# Control.net
KiCad netlist of a schematic drawn in EAGLE
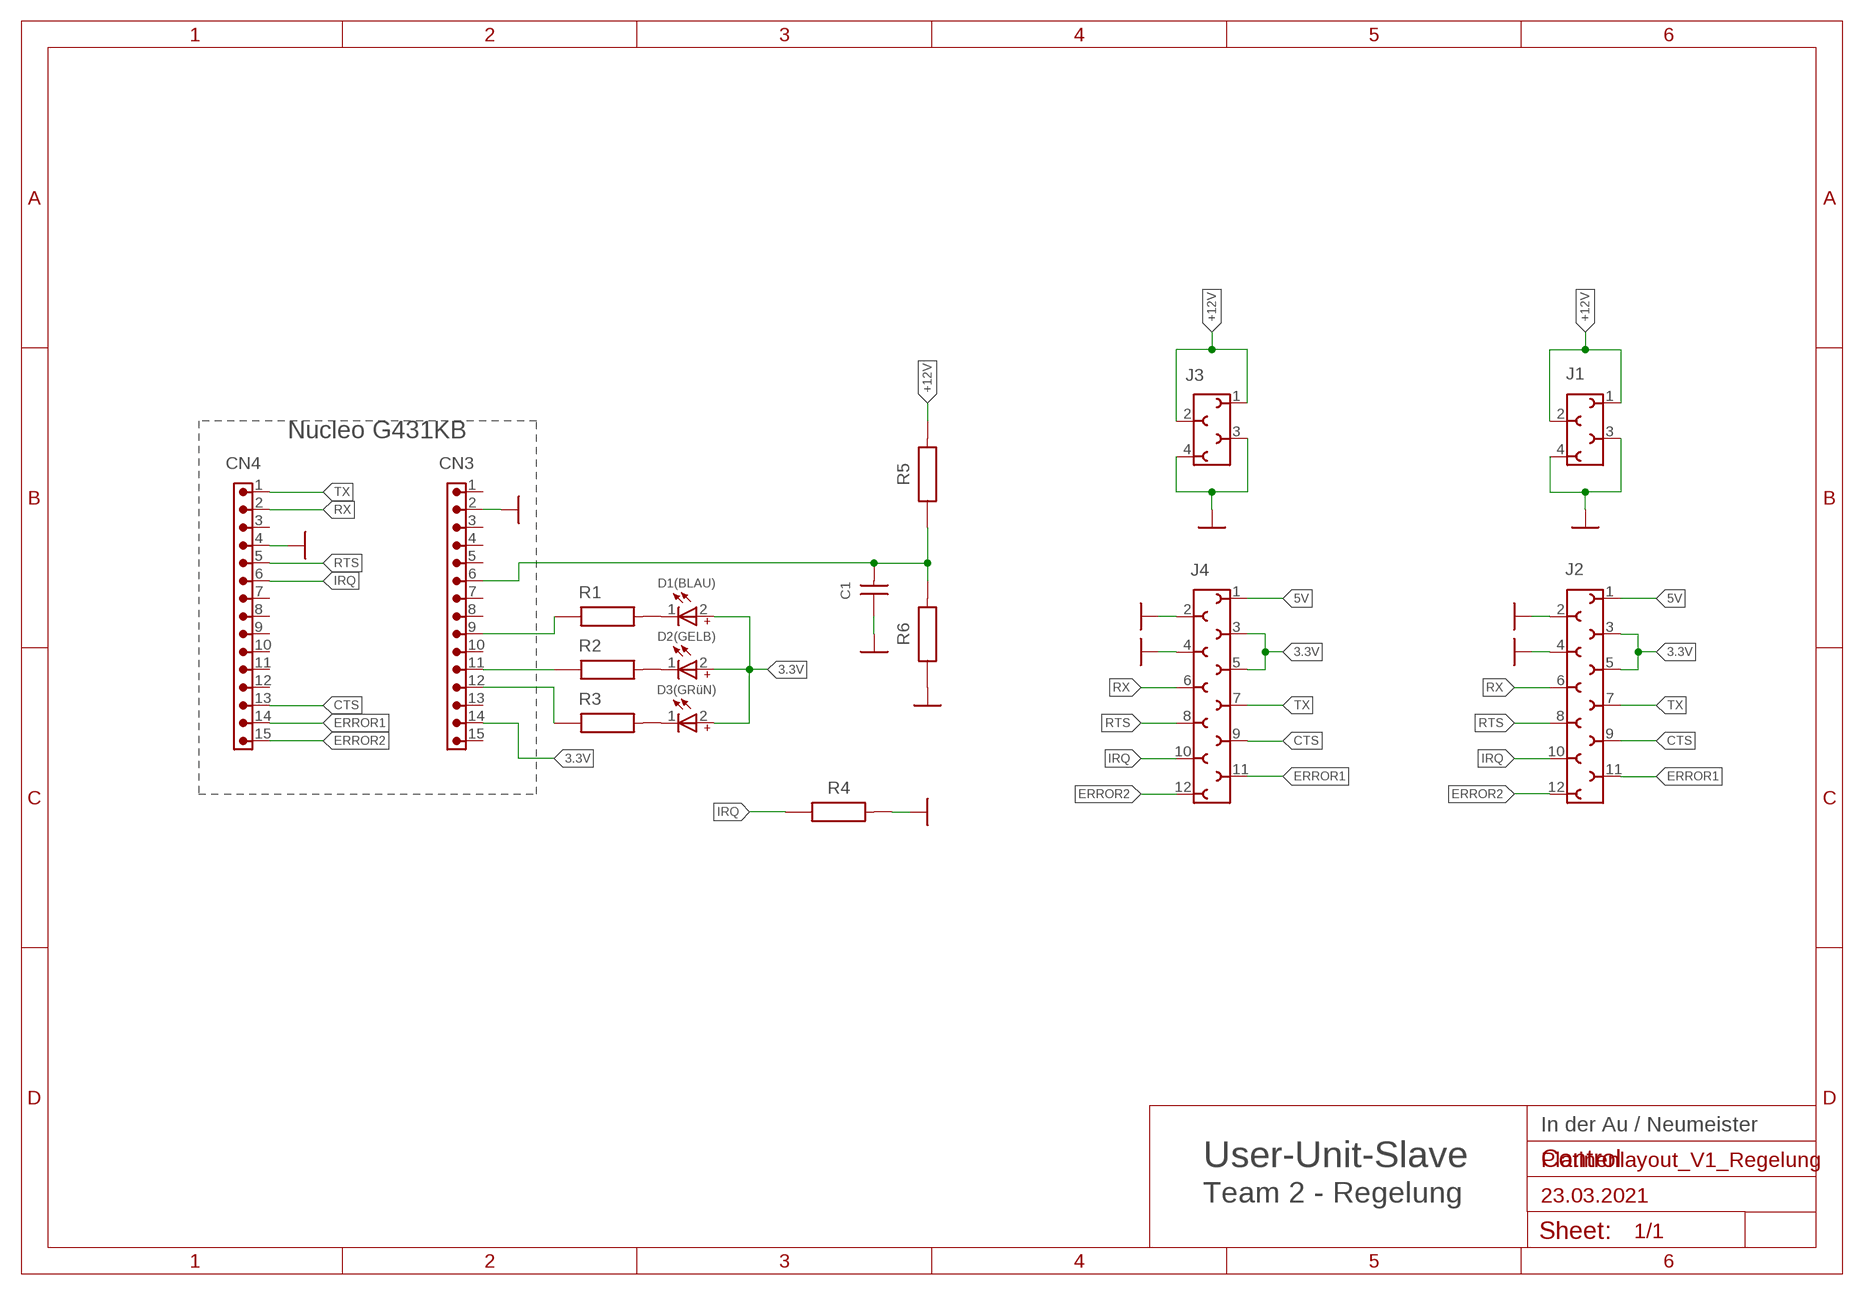
[diagram p0: schematic, sheet 1]

(export (version "E")
  (design (tool "Eeschema 10.0.6"))
  (components
    (comp (ref "C1")
      (value "10 nF")
      (footprint "eagle-import:WCAP-CSGP_1206_H1.25")
      (libsource (lib "eagle-import") (part "WCAP-CSGP_1206_H1.25_10V(DC)_885012008008"))
    )
    (comp (ref "CN3")
      (value "61301511121")
      (footprint "eagle-import:61301511121")
      (libsource (lib "eagle-import") (part "6130XX11121_61301511121"))
    )
    (comp (ref "CN4")
      (value "61301511121")
      (footprint "eagle-import:61301511121")
      (libsource (lib "eagle-import") (part "6130XX11121_61301511121"))
    )
    (comp (ref "D1(BLAU)")
      (value "WL-TMRC_3MM_151031SS06000_WITHOUTSTOPPER")
      (footprint "eagle-import:WL-TMRC_3MM")
      (fields (field (name "SPICEPREFIX") "D"))
      (libsource (lib "eagle-import") (part "WL-TMRC_3MM_WITHOUTSTOPPER_151031SS06000"))
    )
    (comp (ref "D2(GELB)")
      (value "WL-TMRC_3MM_151031YS06000_WITHOUTSTOPPER")
      (footprint "eagle-import:WL-TMRC_3MM")
      (libsource (lib "eagle-import") (part "WL-TMRC_3MM_WITHOUTSTOPPER_151031YS06000"))
    )
    (comp (ref "D3(GRüN)")
      (value "WL-TMRC_3MM_151031VS06000_WITHOUTSTOPPER")
      (footprint "eagle-import:WL-TMRC_3MM")
      (libsource (lib "eagle-import") (part "WL-TMRC_3MM_WITHOUTSTOPPER_151031VS06000"))
    )
    (comp (ref "J1")
      (value "6100XX11921_61000411921")
      (footprint "eagle-import:61000411921")
      (libsource (lib "eagle-import") (part "6100XX11921_61000411921"))
    )
    (comp (ref "J2")
      (value "6100XX11921_61001211921")
      (footprint "eagle-import:61001211921")
      (libsource (lib "eagle-import") (part "6100XX11921_61001211921"))
    )
    (comp (ref "J3")
      (value "690367290476")
      (footprint "eagle-import:690367290476")
      (libsource (lib "eagle-import") (part "690367290476"))
    )
    (comp (ref "J4")
      (value "690367291276")
      (footprint "eagle-import:690367291276")
      (libsource (lib "eagle-import") (part "690367291276"))
    )
    (comp (ref "R1")
      (value "1Ohm")
      (footprint "eagle-import:WRIS-KSKE_0805_2.0X1.25X0.6(LXWXH)")
      (libsource (lib "eagle-import") (part "WRIS-KSKE_0805_2.0X1.25X0.6_560050320011"))
    )
    (comp (ref "R2")
      (value "1Ohm")
      (footprint "eagle-import:WRIS-KSKE_0805_2.0X1.25X0.6(LXWXH)")
      (libsource (lib "eagle-import") (part "WRIS-KSKE_0805_2.0X1.25X0.6_560050320011"))
    )
    (comp (ref "R3")
      (value "1Ohm")
      (footprint "eagle-import:WRIS-KSKE_0805_2.0X1.25X0.6(LXWXH)")
      (libsource (lib "eagle-import") (part "WRIS-KSKE_0805_2.0X1.25X0.6_560050320011"))
    )
    (comp (ref "R4")
      (value "0.1Ohm")
      (footprint "eagle-import:WRIS-KSKE_0805_2.0X1.25X0.6(LXWXH)")
      (libsource (lib "eagle-import") (part "WRIS-KSKE_0805_2.0X1.25X0.6_560050320001"))
    )
    (comp (ref "R5")
      (value "1Ohm")
      (footprint "eagle-import:WRIS-KSKE_0805_2.0X1.25X0.6(LXWXH)")
      (libsource (lib "eagle-import") (part "WRIS-KSKE_0805_2.0X1.25X0.6_560050320011"))
    )
    (comp (ref "R6")
      (value "1Ohm")
      (footprint "eagle-import:WRIS-KSKE_0805_2.0X1.25X0.6(LXWXH)")
      (libsource (lib "eagle-import") (part "WRIS-KSKE_0805_2.0X1.25X0.6_560050320011"))
    )
  )
  (nets
    (net (code "1") (name "+12V") (class "Default")
      (node (ref "J1") (pin "1") (pinfunction "1_1") (pintype "passive"))
      (node (ref "J1") (pin "2") (pinfunction "2_2") (pintype "passive"))
      (node (ref "J3") (pin "1") (pinfunction "1_1") (pintype "passive"))
      (node (ref "J3") (pin "2") (pinfunction "2_2") (pintype "passive"))
      (node (ref "R5") (pin "2") (pinfunction "2_2") (pintype "passive"))
    )
    (net (code "2") (name "3.3V") (class "Default")
      (node (ref "CN3") (pin "14") (pinfunction "14_14") (pintype "passive"))
      (node (ref "D1(BLAU)") (pin "2") (pinfunction "+_2") (pintype "passive"))
      (node (ref "D2(GELB)") (pin "2") (pinfunction "+_2") (pintype "passive"))
      (node (ref "D3(GRüN)") (pin "2") (pinfunction "+_2") (pintype "passive"))
      (node (ref "J2") (pin "3") (pinfunction "3_3") (pintype "passive"))
      (node (ref "J2") (pin "5") (pinfunction "5_5") (pintype "passive"))
      (node (ref "J4") (pin "3") (pinfunction "3_3") (pintype "passive"))
      (node (ref "J4") (pin "5") (pinfunction "5_5") (pintype "passive"))
    )
    (net (code "3") (name "5V") (class "Default")
      (node (ref "J2") (pin "1") (pinfunction "1_1") (pintype "passive"))
      (node (ref "J4") (pin "1") (pinfunction "1_1") (pintype "passive"))
    )
    (net (code "4") (name "CTS") (class "Default")
      (node (ref "CN4") (pin "13") (pinfunction "13_13") (pintype "passive"))
      (node (ref "J2") (pin "9") (pinfunction "9_9") (pintype "passive"))
      (node (ref "J4") (pin "9") (pinfunction "9_9") (pintype "passive"))
    )
    (net (code "5") (name "ERROR1") (class "Default")
      (node (ref "CN4") (pin "14") (pinfunction "14_14") (pintype "passive"))
      (node (ref "J2") (pin "11") (pinfunction "11_11") (pintype "passive"))
      (node (ref "J4") (pin "11") (pinfunction "11_11") (pintype "passive"))
    )
    (net (code "6") (name "ERROR2") (class "Default")
      (node (ref "CN4") (pin "15") (pinfunction "15_15") (pintype "passive"))
      (node (ref "J2") (pin "12") (pinfunction "12_12") (pintype "passive"))
      (node (ref "J4") (pin "12") (pinfunction "12_12") (pintype "passive"))
    )
    (net (code "7") (name "GND") (class "Default")
      (node (ref "C1") (pin "1") (pinfunction "1_1") (pintype "passive"))
      (node (ref "CN3") (pin "2") (pinfunction "2_2") (pintype "passive"))
      (node (ref "CN4") (pin "4") (pinfunction "4_4") (pintype "passive"))
      (node (ref "J1") (pin "3") (pinfunction "3_3") (pintype "passive"))
      (node (ref "J1") (pin "4") (pinfunction "4_4") (pintype "passive"))
      (node (ref "J2") (pin "2") (pinfunction "2_2") (pintype "passive"))
      (node (ref "J2") (pin "4") (pinfunction "4_4") (pintype "passive"))
      (node (ref "J3") (pin "3") (pinfunction "3_3") (pintype "passive"))
      (node (ref "J3") (pin "4") (pinfunction "4_4") (pintype "passive"))
      (node (ref "J4") (pin "2") (pinfunction "2_2") (pintype "passive"))
      (node (ref "J4") (pin "4") (pinfunction "4_4") (pintype "passive"))
      (node (ref "R4") (pin "2") (pinfunction "2_2") (pintype "passive"))
      (node (ref "R6") (pin "1") (pinfunction "1_1") (pintype "passive"))
    )
    (net (code "8") (name "IRQ") (class "Default")
      (node (ref "CN4") (pin "6") (pinfunction "6_6") (pintype "passive"))
      (node (ref "J2") (pin "10") (pinfunction "10_10") (pintype "passive"))
      (node (ref "J4") (pin "10") (pinfunction "10_10") (pintype "passive"))
      (node (ref "R4") (pin "1") (pinfunction "1_1") (pintype "passive"))
    )
    (net (code "9") (name "Net-(C1-Pad2)") (class "Default")
      (node (ref "C1") (pin "2") (pinfunction "2_2") (pintype "passive"))
      (node (ref "CN3") (pin "6") (pinfunction "6_6") (pintype "passive"))
      (node (ref "R5") (pin "1") (pinfunction "1_1") (pintype "passive"))
      (node (ref "R6") (pin "2") (pinfunction "2_2") (pintype "passive"))
    )
    (net (code "10") (name "Net-(CN3-Pad9)") (class "Default")
      (node (ref "CN3") (pin "9") (pinfunction "9_9") (pintype "passive"))
      (node (ref "R1") (pin "1") (pinfunction "1_1") (pintype "passive"))
    )
    (net (code "11") (name "Net-(CN3-Pad11)") (class "Default")
      (node (ref "CN3") (pin "11") (pinfunction "11_11") (pintype "passive"))
      (node (ref "R2") (pin "1") (pinfunction "1_1") (pintype "passive"))
    )
    (net (code "12") (name "Net-(CN3-Pad12)") (class "Default")
      (node (ref "CN3") (pin "12") (pinfunction "12_12") (pintype "passive"))
      (node (ref "R3") (pin "1") (pinfunction "1_1") (pintype "passive"))
    )
    (net (code "13") (name "Net-(D1(BLAU)--)") (class "Default")
      (node (ref "D1(BLAU)") (pin "1") (pinfunction "-_1") (pintype "passive"))
      (node (ref "R1") (pin "2") (pinfunction "2_2") (pintype "passive"))
    )
    (net (code "14") (name "Net-(D2(GELB)--)") (class "Default")
      (node (ref "D2(GELB)") (pin "1") (pinfunction "-_1") (pintype "passive"))
      (node (ref "R2") (pin "2") (pinfunction "2_2") (pintype "passive"))
    )
    (net (code "15") (name "Net-(D3(GRüN)--)") (class "Default")
      (node (ref "D3(GRüN)") (pin "1") (pinfunction "-_1") (pintype "passive"))
      (node (ref "R3") (pin "2") (pinfunction "2_2") (pintype "passive"))
    )
    (net (code "16") (name "RTS") (class "Default")
      (node (ref "CN4") (pin "5") (pinfunction "5_5") (pintype "passive"))
      (node (ref "J2") (pin "8") (pinfunction "8_8") (pintype "passive"))
      (node (ref "J4") (pin "8") (pinfunction "8_8") (pintype "passive"))
    )
    (net (code "17") (name "RX") (class "Default")
      (node (ref "CN4") (pin "2") (pinfunction "2_2") (pintype "passive"))
      (node (ref "J2") (pin "6") (pinfunction "6_6") (pintype "passive"))
      (node (ref "J4") (pin "6") (pinfunction "6_6") (pintype "passive"))
    )
    (net (code "18") (name "TX") (class "Default")
      (node (ref "CN4") (pin "1") (pinfunction "1_1") (pintype "passive"))
      (node (ref "J2") (pin "7") (pinfunction "7_7") (pintype "passive"))
      (node (ref "J4") (pin "7") (pinfunction "7_7") (pintype "passive"))
    )
    (net (code "19") (name "unconnected-(CN3-Pad1)") (class "Default")
      (node (ref "CN3") (pin "1") (pinfunction "1_1") (pintype "passive"))
    )
    (net (code "20") (name "unconnected-(CN3-Pad3)") (class "Default")
      (node (ref "CN3") (pin "3") (pinfunction "3_3") (pintype "passive"))
    )
    (net (code "21") (name "unconnected-(CN3-Pad4)") (class "Default")
      (node (ref "CN3") (pin "4") (pinfunction "4_4") (pintype "passive"))
    )
    (net (code "22") (name "unconnected-(CN3-Pad5)") (class "Default")
      (node (ref "CN3") (pin "5") (pinfunction "5_5") (pintype "passive"))
    )
    (net (code "23") (name "unconnected-(CN3-Pad7)") (class "Default")
      (node (ref "CN3") (pin "7") (pinfunction "7_7") (pintype "passive"))
    )
    (net (code "24") (name "unconnected-(CN3-Pad8)") (class "Default")
      (node (ref "CN3") (pin "8") (pinfunction "8_8") (pintype "passive"))
    )
    (net (code "25") (name "unconnected-(CN3-Pad10)") (class "Default")
      (node (ref "CN3") (pin "10") (pinfunction "10_10") (pintype "passive"))
    )
    (net (code "26") (name "unconnected-(CN3-Pad13)") (class "Default")
      (node (ref "CN3") (pin "13") (pinfunction "13_13") (pintype "passive"))
    )
    (net (code "27") (name "unconnected-(CN3-Pad15)") (class "Default")
      (node (ref "CN3") (pin "15") (pinfunction "15_15") (pintype "passive"))
    )
    (net (code "28") (name "unconnected-(CN4-Pad3)") (class "Default")
      (node (ref "CN4") (pin "3") (pinfunction "3_3") (pintype "passive"))
    )
    (net (code "29") (name "unconnected-(CN4-Pad7)") (class "Default")
      (node (ref "CN4") (pin "7") (pinfunction "7_7") (pintype "passive"))
    )
    (net (code "30") (name "unconnected-(CN4-Pad8)") (class "Default")
      (node (ref "CN4") (pin "8") (pinfunction "8_8") (pintype "passive"))
    )
    (net (code "31") (name "unconnected-(CN4-Pad9)") (class "Default")
      (node (ref "CN4") (pin "9") (pinfunction "9_9") (pintype "passive"))
    )
    (net (code "32") (name "unconnected-(CN4-Pad10)") (class "Default")
      (node (ref "CN4") (pin "10") (pinfunction "10_10") (pintype "passive"))
    )
    (net (code "33") (name "unconnected-(CN4-Pad11)") (class "Default")
      (node (ref "CN4") (pin "11") (pinfunction "11_11") (pintype "passive"))
    )
    (net (code "34") (name "unconnected-(CN4-Pad12)") (class "Default")
      (node (ref "CN4") (pin "12") (pinfunction "12_12") (pintype "passive"))
    )
  )
)
